# Pro1.net
KiCad netlist of a schematic drawn in EAGLE
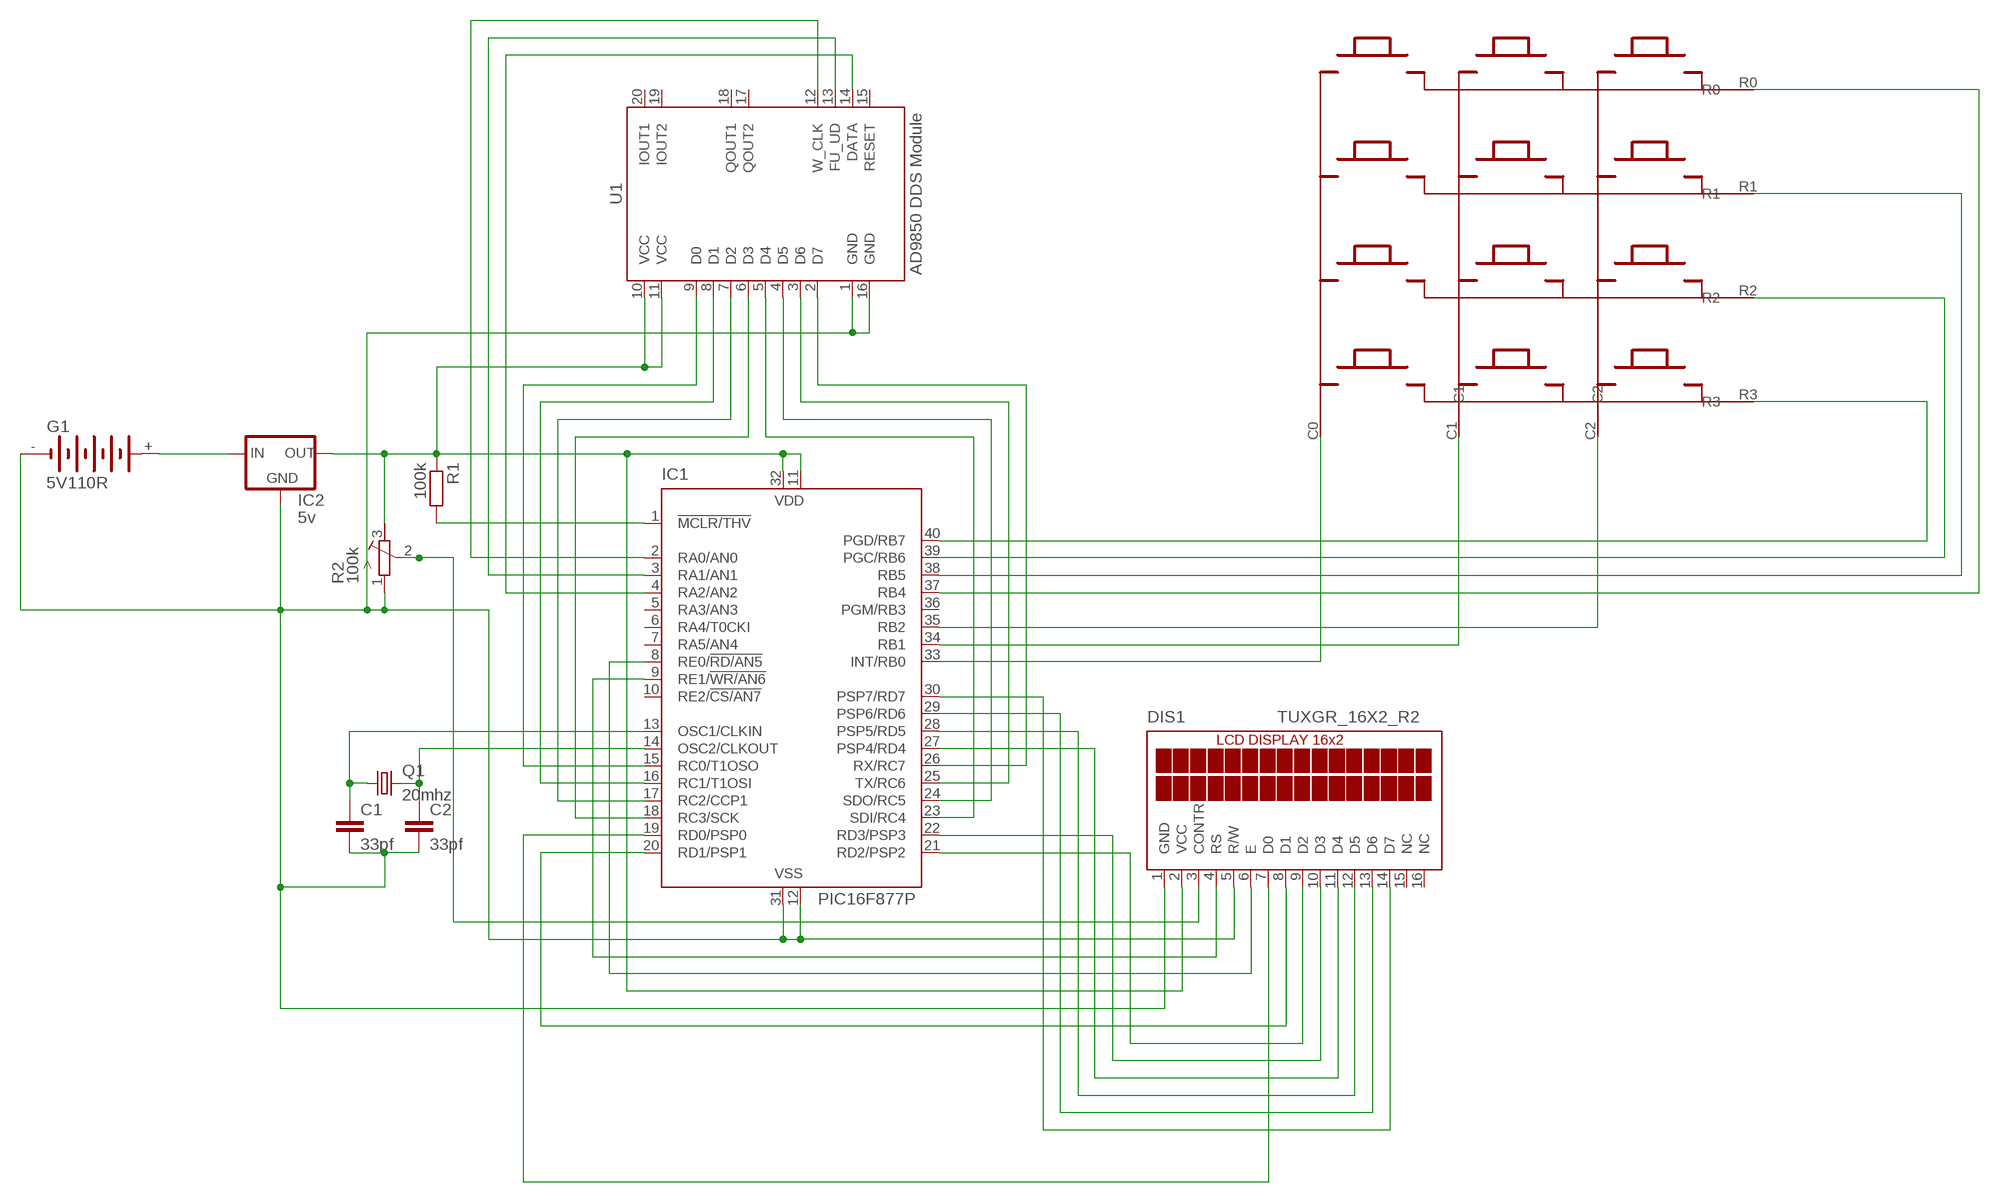
[diagram p0: schematic, sheet 1]

(export (version "E")
  (design (tool "Eeschema 10.0.6"))
  (components
    (comp (ref "C1")
      (value "33pf")
      (footprint "eagle-import:C2.5-3")
      (libsource (lib "eagle-import") (part "C2,5-3"))
    )
    (comp (ref "C2")
      (value "33pf")
      (footprint "eagle-import:C2.5-3")
      (libsource (lib "eagle-import") (part "C2,5-3"))
    )
    (comp (ref "DIS1")
      (value "TUXGR_16X2_R2")
      (footprint "eagle-import:TUXGR_16X2_R2")
      (libsource (lib "eagle-import") (part "TUXGR_16X2_R2"))
    )
    (comp (ref "G1")
      (value "5V110R")
      (footprint "eagle-import:5V110R")
      (libsource (lib "eagle-import") (part "5V110R"))
    )
    (comp (ref "IC1")
      (value "PIC16F877P")
      (footprint "eagle-import:DIL40")
      (fields (field (name "MF") "MICROCHIP") (field (name "MPN") "PIC16F877-04/P"))
      (libsource (lib "eagle-import") (part "PIC16F87P7"))
    )
    (comp (ref "IC2")
      (value "5v")
      (footprint "eagle-import:78XXL")
      (libsource (lib "eagle-import") (part "78XXL"))
    )
    (comp (ref "KP1")
      (value "KEYPAD")
      (footprint "eagle-import:KEYPAD")
      (libsource (lib "eagle-import") (part "KEYPAD"))
    )
    (comp (ref "Q1")
      (value "20mhz")
      (footprint "eagle-import:HC49U-V")
      (libsource (lib "eagle-import") (part "CRYSTALHC49U-V"))
    )
    (comp (ref "R1")
      (value "100k")
      (footprint "eagle-import:0204_7")
      (libsource (lib "eagle-import") (part "R-EU_0204/7"))
    )
    (comp (ref "R2")
      (value "100k")
      (footprint "eagle-import:RTRIM74X")
      (libsource (lib "eagle-import") (part "R-TRIMM74X"))
    )
    (comp (ref "U1")
      (value "AD9850 DDS Module")
      (footprint "eagle-import:DDS_AD9850")
      (libsource (lib "eagle-import") (part "DDS_MODULE{colon}AD9850DDS_MODULE"))
    )
  )
  (nets
    (net (code "1") (name "Net-(DIS1-CONTR)") (class "Default")
      (node (ref "DIS1") (pin "3") (pinfunction "CONTR_3") (pintype "input"))
      (node (ref "R2") (pin "2") (pinfunction "S_2") (pintype "passive"))
    )
    (net (code "2") (name "Net-(DIS1-D0)") (class "Default")
      (node (ref "DIS1") (pin "7") (pinfunction "D0_7") (pintype "input"))
      (node (ref "IC1") (pin "19") (pinfunction "RD0/PSP0_19") (pintype "bidirectional"))
    )
    (net (code "3") (name "Net-(DIS1-D1)") (class "Default")
      (node (ref "DIS1") (pin "8") (pinfunction "D1_8") (pintype "input"))
      (node (ref "IC1") (pin "20") (pinfunction "RD1/PSP1_20") (pintype "bidirectional"))
    )
    (net (code "4") (name "Net-(DIS1-D2)") (class "Default")
      (node (ref "DIS1") (pin "9") (pinfunction "D2_9") (pintype "input"))
      (node (ref "IC1") (pin "21") (pinfunction "RD2/PSP2_21") (pintype "bidirectional"))
    )
    (net (code "5") (name "Net-(DIS1-D3)") (class "Default")
      (node (ref "DIS1") (pin "10") (pinfunction "D3_10") (pintype "input"))
      (node (ref "IC1") (pin "22") (pinfunction "RD3/PSP3_22") (pintype "bidirectional"))
    )
    (net (code "6") (name "Net-(DIS1-D4)") (class "Default")
      (node (ref "DIS1") (pin "11") (pinfunction "D4_11") (pintype "input"))
      (node (ref "IC1") (pin "27") (pinfunction "PSP4/RD4_27") (pintype "bidirectional"))
    )
    (net (code "7") (name "Net-(DIS1-D5)") (class "Default")
      (node (ref "DIS1") (pin "12") (pinfunction "D5_12") (pintype "input"))
      (node (ref "IC1") (pin "28") (pinfunction "PSP5/RD5_28") (pintype "bidirectional"))
    )
    (net (code "8") (name "Net-(DIS1-D6)") (class "Default")
      (node (ref "DIS1") (pin "13") (pinfunction "D6_13") (pintype "input"))
      (node (ref "IC1") (pin "29") (pinfunction "PSP6/RD6_29") (pintype "bidirectional"))
    )
    (net (code "9") (name "Net-(DIS1-D7)") (class "Default")
      (node (ref "DIS1") (pin "14") (pinfunction "D7_14") (pintype "input"))
      (node (ref "IC1") (pin "30") (pinfunction "PSP7/RD7_30") (pintype "bidirectional"))
    )
    (net (code "10") (name "Net-(DIS1-E)") (class "Default")
      (node (ref "DIS1") (pin "6") (pinfunction "E_6") (pintype "input"))
      (node (ref "IC1") (pin "8") (pinfunction "RE0/~{RD/AN5}_8") (pintype "bidirectional"))
    )
    (net (code "11") (name "Net-(DIS1-GND)") (class "Default")
      (node (ref "C1") (pin "2") (pinfunction "2_2") (pintype "passive"))
      (node (ref "C2") (pin "2") (pinfunction "2_2") (pintype "passive"))
      (node (ref "DIS1") (pin "1") (pinfunction "GND_1") (pintype "power_in"))
      (node (ref "DIS1") (pin "5") (pinfunction "R/W_5") (pintype "input"))
      (node (ref "G1") (pin "-") (pinfunction "-_-") (pintype "passive"))
      (node (ref "IC1") (pin "12") (pinfunction "VSS_12") (pintype "power_in"))
      (node (ref "IC1") (pin "31") (pinfunction "VSS_31") (pintype "power_in"))
      (node (ref "IC2") (pin "GND") (pinfunction "GND_GND") (pintype "input"))
      (node (ref "R2") (pin "1") (pinfunction "A_1") (pintype "passive"))
      (node (ref "U1") (pin "1") (pinfunction "GND_1") (pintype "power_in"))
      (node (ref "U1") (pin "16") (pinfunction "GND_16") (pintype "power_in"))
    )
    (net (code "12") (name "Net-(DIS1-RS)") (class "Default")
      (node (ref "DIS1") (pin "4") (pinfunction "RS_4") (pintype "input"))
      (node (ref "IC1") (pin "9") (pinfunction "RE1/~{WR/AN6}_9") (pintype "bidirectional"))
    )
    (net (code "13") (name "Net-(DIS1-VCC)") (class "Default")
      (node (ref "DIS1") (pin "2") (pinfunction "VCC_2") (pintype "power_in"))
      (node (ref "IC1") (pin "11") (pinfunction "VDD_11") (pintype "power_in"))
      (node (ref "IC1") (pin "32") (pinfunction "VDD_32") (pintype "power_in"))
      (node (ref "IC2") (pin "OUT") (pinfunction "OUT_OUT") (pintype "passive"))
      (node (ref "R1") (pin "1") (pinfunction "1_1") (pintype "passive"))
      (node (ref "R2") (pin "3") (pinfunction "E_3") (pintype "passive"))
      (node (ref "U1") (pin "10") (pinfunction "VCC_10") (pintype "power_in"))
      (node (ref "U1") (pin "11") (pinfunction "VCC_11") (pintype "power_in"))
    )
    (net (code "14") (name "Net-(G1-Pad+)") (class "Default")
      (node (ref "G1") (pin "+") (pinfunction "+_+") (pintype "passive"))
      (node (ref "IC2") (pin "IN") (pinfunction "IN_IN") (pintype "input"))
    )
    (net (code "15") (name "Net-(IC1-INT{slash}RB0)") (class "Default")
      (node (ref "IC1") (pin "33") (pinfunction "INT/RB0_33") (pintype "bidirectional"))
      (node (ref "KP1") (pin "C0") (pinfunction "C0_C0") (pintype "bidirectional"))
    )
    (net (code "16") (name "Net-(IC1-OSC1{slash}CLKIN)") (class "Default")
      (node (ref "C1") (pin "1") (pinfunction "1_1") (pintype "passive"))
      (node (ref "IC1") (pin "13") (pinfunction "OSC1/CLKIN_13") (pintype "input"))
      (node (ref "Q1") (pin "1") (pinfunction "1_1") (pintype "passive"))
    )
    (net (code "17") (name "Net-(IC1-OSC2{slash}CLKOUT)") (class "Default")
      (node (ref "C2") (pin "1") (pinfunction "1_1") (pintype "passive"))
      (node (ref "IC1") (pin "14") (pinfunction "OSC2/CLKOUT_14") (pintype "output"))
      (node (ref "Q1") (pin "2") (pinfunction "2_2") (pintype "passive"))
    )
    (net (code "18") (name "Net-(IC1-PGC{slash}RB6)") (class "Default")
      (node (ref "IC1") (pin "39") (pinfunction "PGC/RB6_39") (pintype "bidirectional"))
      (node (ref "KP1") (pin "R2") (pinfunction "R2_R2") (pintype "bidirectional"))
    )
    (net (code "19") (name "Net-(IC1-PGD{slash}RB7)") (class "Default")
      (node (ref "IC1") (pin "40") (pinfunction "PGD/RB7_40") (pintype "bidirectional"))
      (node (ref "KP1") (pin "R3") (pinfunction "R3_R3") (pintype "bidirectional"))
    )
    (net (code "20") (name "Net-(IC1-RA0{slash}AN0)") (class "Default")
      (node (ref "IC1") (pin "2") (pinfunction "RA0/AN0_2") (pintype "bidirectional"))
      (node (ref "U1") (pin "12") (pinfunction "W_CLK_12") (pintype "input"))
    )
    (net (code "21") (name "Net-(IC1-RA1{slash}AN1)") (class "Default")
      (node (ref "IC1") (pin "3") (pinfunction "RA1/AN1_3") (pintype "bidirectional"))
      (node (ref "U1") (pin "13") (pinfunction "FU_UD_13") (pintype "input"))
    )
    (net (code "22") (name "Net-(IC1-RA2{slash}AN2)") (class "Default")
      (node (ref "IC1") (pin "4") (pinfunction "RA2/AN2_4") (pintype "bidirectional"))
      (node (ref "U1") (pin "14") (pinfunction "DATA_14") (pintype "input"))
    )
    (net (code "23") (name "Net-(IC1-RB1)") (class "Default")
      (node (ref "IC1") (pin "34") (pinfunction "RB1_34") (pintype "bidirectional"))
      (node (ref "KP1") (pin "C1") (pinfunction "C1_C1") (pintype "bidirectional"))
    )
    (net (code "24") (name "Net-(IC1-RB2)") (class "Default")
      (node (ref "IC1") (pin "35") (pinfunction "RB2_35") (pintype "bidirectional"))
      (node (ref "KP1") (pin "C2") (pinfunction "C2_C2") (pintype "bidirectional"))
    )
    (net (code "25") (name "Net-(IC1-RB4)") (class "Default")
      (node (ref "IC1") (pin "37") (pinfunction "RB4_37") (pintype "bidirectional"))
      (node (ref "KP1") (pin "R0") (pinfunction "R0_R0") (pintype "bidirectional"))
    )
    (net (code "26") (name "Net-(IC1-RB5)") (class "Default")
      (node (ref "IC1") (pin "38") (pinfunction "RB5_38") (pintype "bidirectional"))
      (node (ref "KP1") (pin "R1") (pinfunction "R1_R1") (pintype "bidirectional"))
    )
    (net (code "27") (name "Net-(IC1-RC0{slash}T1OSO)") (class "Default")
      (node (ref "IC1") (pin "15") (pinfunction "RC0/T1OSO_15") (pintype "bidirectional"))
      (node (ref "U1") (pin "9") (pinfunction "D0_9") (pintype "input"))
    )
    (net (code "28") (name "Net-(IC1-RC1{slash}T1OSI)") (class "Default")
      (node (ref "IC1") (pin "16") (pinfunction "RC1/T1OSI_16") (pintype "bidirectional"))
      (node (ref "U1") (pin "8") (pinfunction "D1_8") (pintype "input"))
    )
    (net (code "29") (name "Net-(IC1-RC2{slash}CCP1)") (class "Default")
      (node (ref "IC1") (pin "17") (pinfunction "RC2/CCP1_17") (pintype "bidirectional"))
      (node (ref "U1") (pin "7") (pinfunction "D2_7") (pintype "input"))
    )
    (net (code "30") (name "Net-(IC1-RC3{slash}SCK)") (class "Default")
      (node (ref "IC1") (pin "18") (pinfunction "RC3/SCK_18") (pintype "bidirectional"))
      (node (ref "U1") (pin "6") (pinfunction "D3_6") (pintype "input"))
    )
    (net (code "31") (name "Net-(IC1-RX{slash}RC7)") (class "Default")
      (node (ref "IC1") (pin "26") (pinfunction "RX/RC7_26") (pintype "bidirectional"))
      (node (ref "U1") (pin "2") (pinfunction "D7_2") (pintype "input"))
    )
    (net (code "32") (name "Net-(IC1-SDI{slash}RC4)") (class "Default")
      (node (ref "IC1") (pin "23") (pinfunction "SDI/RC4_23") (pintype "bidirectional"))
      (node (ref "U1") (pin "5") (pinfunction "D4_5") (pintype "input"))
    )
    (net (code "33") (name "Net-(IC1-SDO{slash}RC5)") (class "Default")
      (node (ref "IC1") (pin "24") (pinfunction "SDO/RC5_24") (pintype "bidirectional"))
      (node (ref "U1") (pin "4") (pinfunction "D5_4") (pintype "input"))
    )
    (net (code "34") (name "Net-(IC1-TX{slash}RC6)") (class "Default")
      (node (ref "IC1") (pin "25") (pinfunction "TX/RC6_25") (pintype "bidirectional"))
      (node (ref "U1") (pin "3") (pinfunction "D6_3") (pintype "input"))
    )
    (net (code "35") (name "Net-(IC1-~{MCLR{slash}THV})") (class "Default")
      (node (ref "IC1") (pin "1") (pinfunction "~{MCLR/THV}_1") (pintype "input"))
      (node (ref "R1") (pin "2") (pinfunction "2_2") (pintype "passive"))
    )
    (net (code "36") (name "unconnected-(DIS1-NC-Pad15)") (class "Default")
      (node (ref "DIS1") (pin "15") (pinfunction "NC_15") (pintype "no_connect"))
    )
    (net (code "37") (name "unconnected-(DIS1-NC-Pad16)") (class "Default")
      (node (ref "DIS1") (pin "16") (pinfunction "NC_16") (pintype "no_connect"))
    )
    (net (code "38") (name "unconnected-(G1-+-Pad+@1)") (class "Default")
      (node (ref "G1") (pin "+@1") (pinfunction "+_+@1") (pintype "passive"))
    )
    (net (code "39") (name "unconnected-(IC1-PGM{slash}RB3-Pad36)") (class "Default")
      (node (ref "IC1") (pin "36") (pinfunction "PGM/RB3_36") (pintype "bidirectional"))
    )
    (net (code "40") (name "unconnected-(IC1-RA3{slash}AN3-Pad5)") (class "Default")
      (node (ref "IC1") (pin "5") (pinfunction "RA3/AN3_5") (pintype "bidirectional"))
    )
    (net (code "41") (name "unconnected-(IC1-RA4{slash}T0CKI-Pad6)") (class "Default")
      (node (ref "IC1") (pin "6") (pinfunction "RA4/T0CKI_6") (pintype "bidirectional"))
    )
    (net (code "42") (name "unconnected-(IC1-RA5{slash}AN4-Pad7)") (class "Default")
      (node (ref "IC1") (pin "7") (pinfunction "RA5/AN4_7") (pintype "bidirectional"))
    )
    (net (code "43") (name "unconnected-(IC1-RE2{slash}~{CS{slash}AN7}-Pad10)") (class "Default")
      (node (ref "IC1") (pin "10") (pinfunction "RE2/~{CS/AN7}_10") (pintype "bidirectional"))
    )
    (net (code "44") (name "unconnected-(U1-IOUT1-Pad20)") (class "Default")
      (node (ref "U1") (pin "20") (pinfunction "IOUT1_20") (pintype "output"))
    )
    (net (code "45") (name "unconnected-(U1-IOUT2-Pad19)") (class "Default")
      (node (ref "U1") (pin "19") (pinfunction "IOUT2_19") (pintype "output"))
    )
    (net (code "46") (name "unconnected-(U1-QOUT1-Pad18)") (class "Default")
      (node (ref "U1") (pin "18") (pinfunction "QOUT1_18") (pintype "output"))
    )
    (net (code "47") (name "unconnected-(U1-QOUT2-Pad17)") (class "Default")
      (node (ref "U1") (pin "17") (pinfunction "QOUT2_17") (pintype "output"))
    )
    (net (code "48") (name "unconnected-(U1-RESET-Pad15)") (class "Default")
      (node (ref "U1") (pin "15") (pinfunction "RESET_15") (pintype "bidirectional"))
    )
  )
)
